# Group12_411_REV3.net
KiCad netlist of a schematic drawn in EAGLE
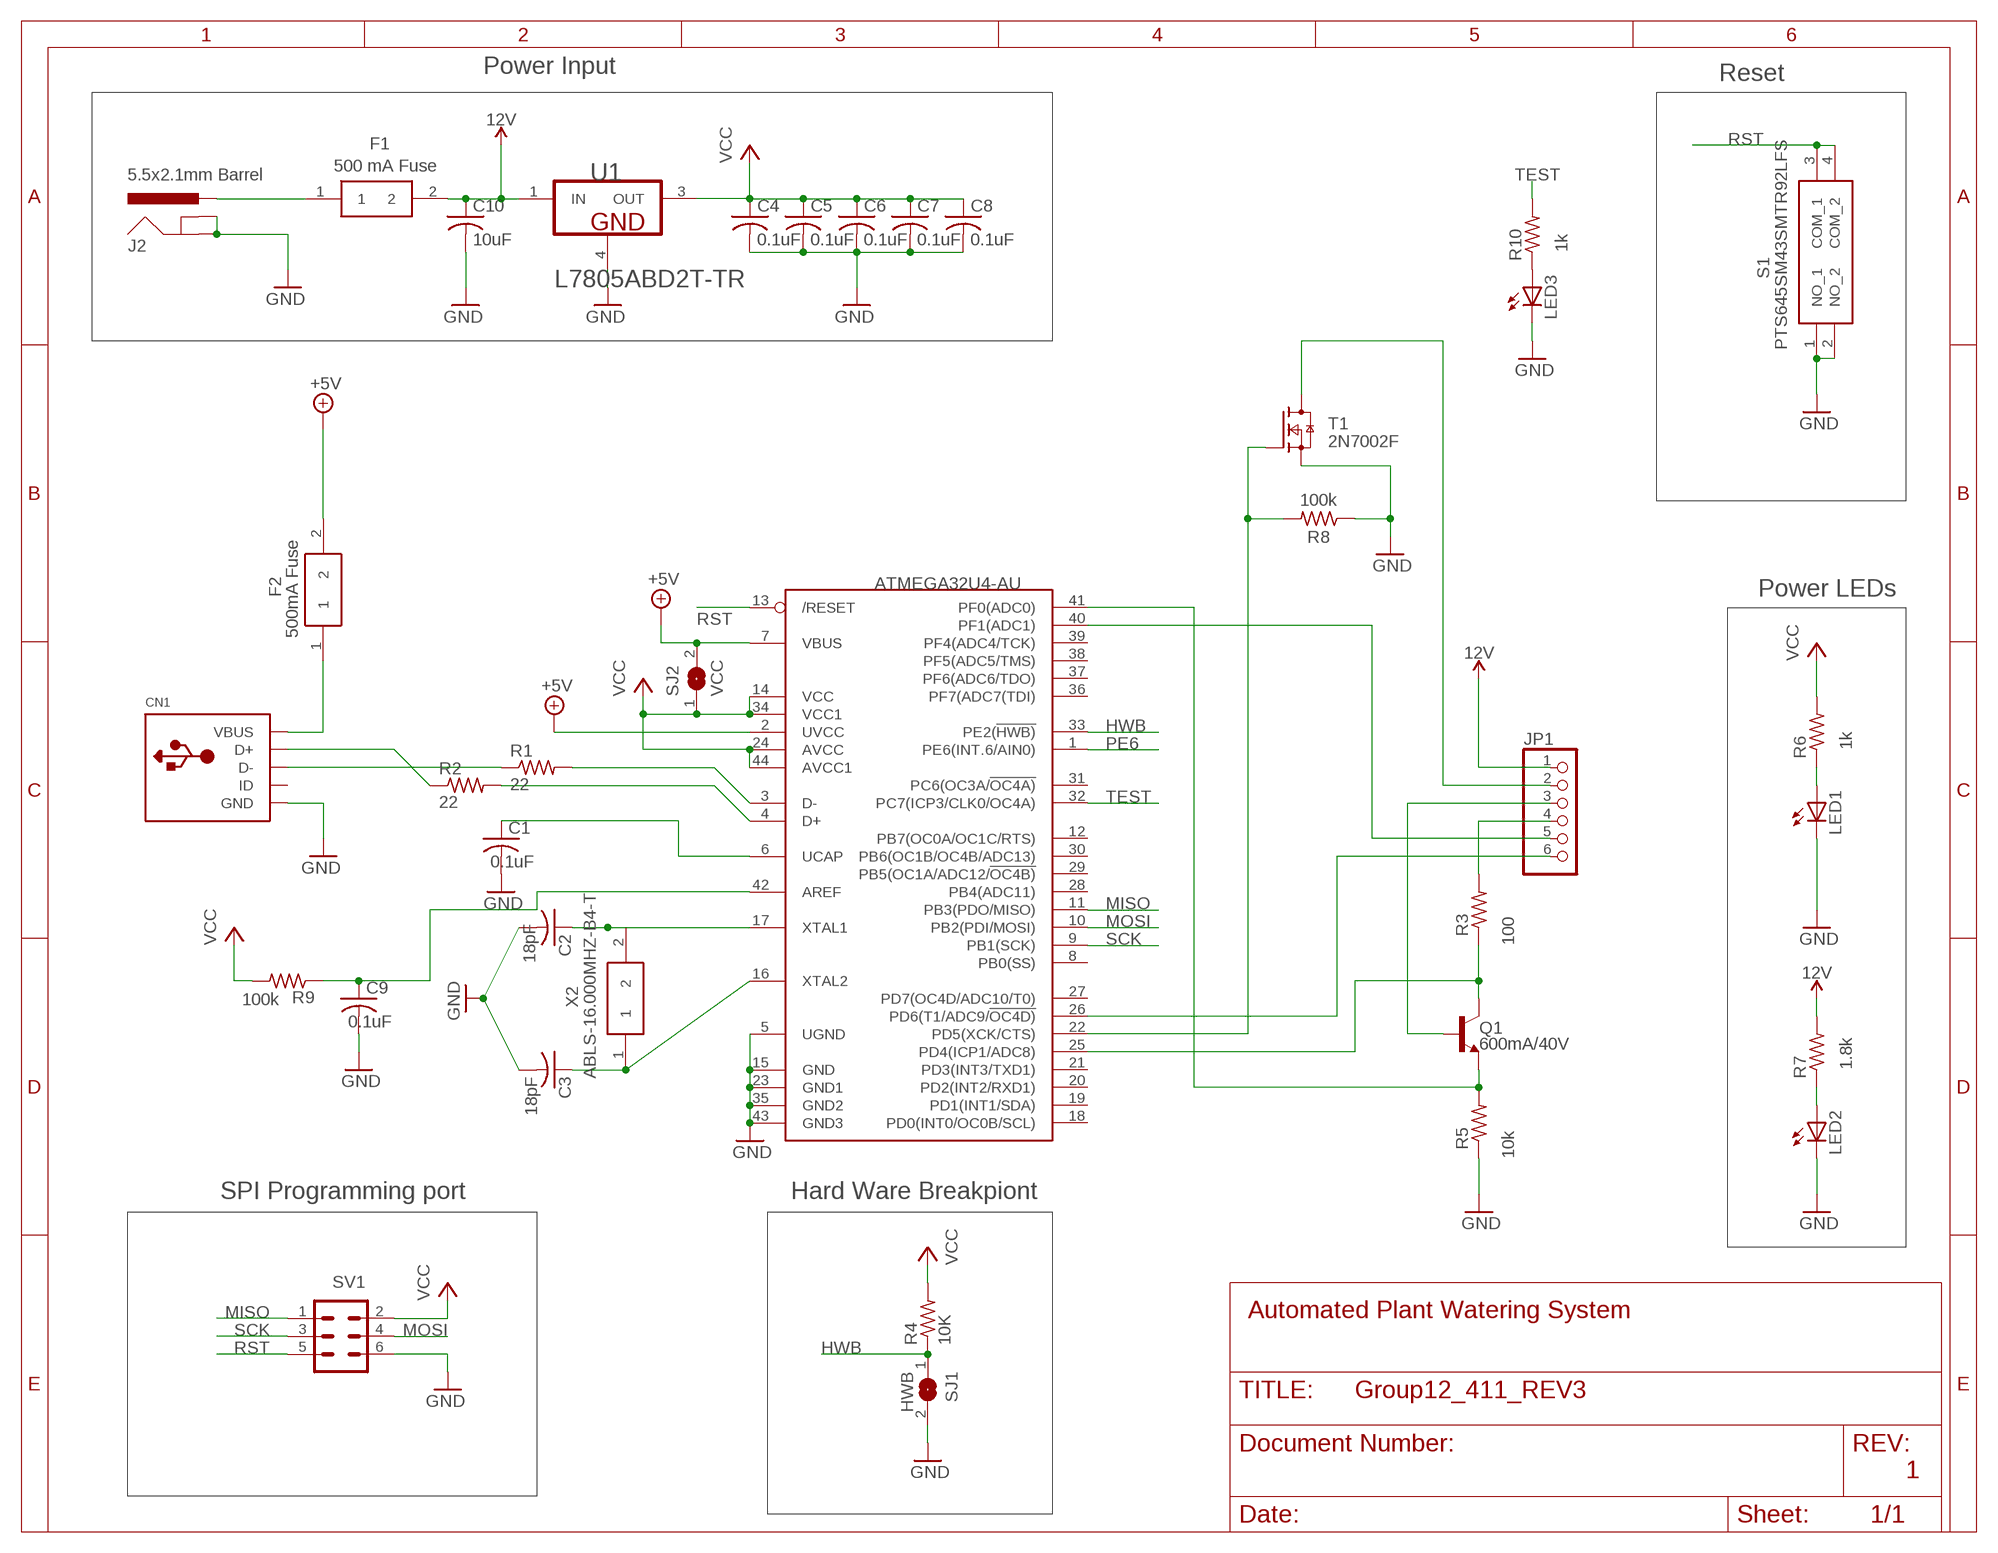
[diagram p0: schematic, sheet 1]

(export (version "E")
  (design (tool "Eeschema 10.0.6"))
  (components
    (comp (ref "C1")
      (value "0.1uF")
      (footprint "eagle-import:C0805K")
      (libsource (lib "eagle-import") (part "C-USC0805K"))
    )
    (comp (ref "C2")
      (value "18pF")
      (footprint "eagle-import:C0805K")
      (libsource (lib "eagle-import") (part "C-USC0805K"))
    )
    (comp (ref "C3")
      (value "18pF")
      (footprint "eagle-import:C0805K")
      (libsource (lib "eagle-import") (part "C-USC0805K"))
    )
    (comp (ref "C4")
      (value "0.1uF")
      (footprint "eagle-import:C0805K")
      (libsource (lib "eagle-import") (part "C-USC0805K"))
    )
    (comp (ref "C5")
      (value "0.1uF")
      (footprint "eagle-import:C0805K")
      (libsource (lib "eagle-import") (part "C-USC0805K"))
    )
    (comp (ref "C6")
      (value "0.1uF")
      (footprint "eagle-import:C0805K")
      (libsource (lib "eagle-import") (part "C-USC0805K"))
    )
    (comp (ref "C7")
      (value "0.1uF")
      (footprint "eagle-import:C0805K")
      (libsource (lib "eagle-import") (part "C-USC0805K"))
    )
    (comp (ref "C8")
      (value "0.1uF")
      (footprint "eagle-import:C0805K")
      (libsource (lib "eagle-import") (part "C-USC0805K"))
    )
    (comp (ref "C9")
      (value "0.1uF")
      (footprint "eagle-import:C0805K")
      (libsource (lib "eagle-import") (part "C-USC0805K"))
    )
    (comp (ref "C10")
      (value "10uF")
      (footprint "eagle-import:C0805K")
      (libsource (lib "eagle-import") (part "C-USC0805K"))
    )
    (comp (ref "CN1")
      (value "USBMINIB")
      (footprint "eagle-import:USB-MINIB")
      (libsource (lib "eagle-import") (part "USBMINIB"))
    )
    (comp (ref "F1")
      (value "MFU0805FF00500P100")
      (footprint "eagle-import:FUSC2012X55N")
      (fields
        (field (name "MANUFACTURER_PART_NUMBER") "MFU0805FF00500P100")
        (field (name "MOUSER_PART_NUMBER") "594-MFU0805FF00500P1")
        (field (name "MANUFACTURER_PART_NUMBER_1") "500 mA Fuse")
      )
      (libsource (lib "eagle-import") (part "MFU0805FF00500P100"))
    )
    (comp (ref "F2")
      (value "MFU0805FF00500P100")
      (footprint "eagle-import:FUSC2012X55N")
      (fields
        (field (name "MANUFACTURER_PART_NUMBER") "MFU0805FF00500P100")
        (field (name "MOUSER_PART_NUMBER") "594-MFU0805FF00500P1")
        (field (name "MANUFACTURER_PART_NUMBER_1") "500mA Fuse")
      )
      (libsource (lib "eagle-import") (part "MFU0805FF00500P100"))
    )
    (comp (ref "J2")
      (value "5.5x2.1mm Barrel")
      (footprint "eagle-import:POWER_JACK_SMD")
      (libsource (lib "eagle-import") (part "POWER_JACKSMD"))
    )
    (comp (ref "JP1")
      (value "PINHD-1X6-3.5MM")
      (footprint "eagle-import:1X06-3.5MM")
      (libsource (lib "eagle-import") (part "PINHD-1X6-3.5MM"))
    )
    (comp (ref "LED1")
      (value "LEDCHIP-LED0603")
      (footprint "eagle-import:CHIP-LED0603")
      (libsource (lib "eagle-import") (part "LEDCHIP-LED0603"))
    )
    (comp (ref "LED2")
      (value "LEDCHIP-LED0603")
      (footprint "eagle-import:CHIP-LED0603")
      (libsource (lib "eagle-import") (part "LEDCHIP-LED0603"))
    )
    (comp (ref "LED3")
      (value "LEDCHIP-LED0603")
      (footprint "eagle-import:CHIP-LED0603")
      (libsource (lib "eagle-import") (part "LEDCHIP-LED0603"))
    )
    (comp (ref "Q1")
      (value "600mA/40V")
      (footprint "eagle-import:SOT23-3")
      (libsource (lib "eagle-import") (part "TRANS_NPN-MMBT2222AL"))
    )
    (comp (ref "R1")
      (value "22")
      (footprint "eagle-import:R0805")
      (libsource (lib "eagle-import") (part "R-US_R0805"))
    )
    (comp (ref "R2")
      (value "22")
      (footprint "eagle-import:R0805")
      (libsource (lib "eagle-import") (part "R-US_R0805"))
    )
    (comp (ref "R3")
      (value "22")
      (footprint "eagle-import:R0805")
      (fields (field (name "R") "100"))
      (libsource (lib "eagle-import") (part "R-US_R0805"))
    )
    (comp (ref "R4")
      (value "10K")
      (footprint "eagle-import:R0805")
      (libsource (lib "eagle-import") (part "R-US_R0805"))
    )
    (comp (ref "R5")
      (value "22")
      (footprint "eagle-import:R0805")
      (fields (field (name "R") "10k"))
      (libsource (lib "eagle-import") (part "R-US_R0805"))
    )
    (comp (ref "R6")
      (value "10K")
      (footprint "eagle-import:R0805")
      (fields (field (name "R") "1k"))
      (libsource (lib "eagle-import") (part "R-US_R0805"))
    )
    (comp (ref "R7")
      (value "10K")
      (footprint "eagle-import:R0805")
      (fields (field (name "R") "1.8k"))
      (libsource (lib "eagle-import") (part "R-US_R0805"))
    )
    (comp (ref "R8")
      (value "10K")
      (footprint "eagle-import:R0805")
      (fields (field (name "R") "100k"))
      (libsource (lib "eagle-import") (part "R-US_R0805"))
    )
    (comp (ref "R9")
      (value "100k")
      (footprint "eagle-import:R0805")
      (libsource (lib "eagle-import") (part "R-US_R0805"))
    )
    (comp (ref "R10")
      (value "10K")
      (footprint "eagle-import:R0805")
      (fields (field (name "R") "1k"))
      (libsource (lib "eagle-import") (part "R-US_R0805"))
    )
    (comp (ref "S1")
      (value "PTS645SM43SMTR92LFS")
      (footprint "eagle-import:PTS645SMT")
      (fields (field (name "MOUSER_PART_NUMBER") "611-PTS645SM43SMTR92"))
      (libsource (lib "eagle-import") (part "PTS645SM43SMTR92LFS"))
    )
    (comp (ref "SJ1")
      (value "HWB")
      (footprint "eagle-import:SJ")
      (libsource (lib "eagle-import") (part "SJ"))
    )
    (comp (ref "SJ2")
      (value "VCC")
      (footprint "eagle-import:SJ")
      (libsource (lib "eagle-import") (part "SJ"))
    )
    (comp (ref "SV1")
      (value "MA03-2")
      (footprint "eagle-import:MA03-2")
      (libsource (lib "eagle-import") (part "MA03-2"))
    )
    (comp (ref "T1")
      (value "2N7002F")
      (footprint "eagle-import:SOT23")
      (libsource (lib "eagle-import") (part "2N7002F"))
    )
    (comp (ref "U1")
      (value "STMICROELECTRONICS_L7805ABD2T-TRSTMICROELECTRONICS_L7805ABD2T-TR_0_0")
      (footprint "eagle-import:STMICROELECTRONICS_L7805ABD2T-TR_0")
      (fields (field (name "MF") "STMicroelectronics") (field (name "MPN") "L7805ABD2T-TR"))
      (libsource (lib "eagle-import") (part "STMICROELECTRONICS_L7805ABD2T-TRSTMICROELECTRONICS_L7805ABD2T-TR_0_0"))
    )
    (comp (ref "U2")
      (value "ATMEGA32U4-AU")
      (footprint "eagle-import:TQFP44")
      (libsource (lib "eagle-import") (part "ATMEGA32U4-AU"))
    )
    (comp (ref "X2")
      (value "ABLS-16.000MHZ-B4-T")
      (footprint "eagle-import:ABLS")
      (fields (field (name "MOUSER_PART_NUMBER") "815-ABLS-16.0M-T"))
      (libsource (lib "eagle-import") (part "ABLS-16.000MHZ-B4-T"))
    )
  )
  (nets
    (net (code "1") (name "+5V") (class "Default")
      (node (ref "F2") (pin "2") (pinfunction "2_2") (pintype "bidirectional"))
      (node (ref "SJ2") (pin "2") (pinfunction "2_2") (pintype "passive"))
      (node (ref "U2") (pin "2") (pinfunction "UVCC_2") (pintype "bidirectional"))
      (node (ref "U2") (pin "7") (pinfunction "VBUS_7") (pintype "bidirectional"))
    )
    (net (code "2") (name "/HWB") (class "Default")
      (node (ref "R4") (pin "1") (pinfunction "1_1") (pintype "passive"))
      (node (ref "SJ1") (pin "1") (pinfunction "1_1") (pintype "passive"))
      (node (ref "U2") (pin "33") (pinfunction "PE2(~{HWB})_33") (pintype "bidirectional"))
    )
    (net (code "3") (name "/MISO") (class "Default")
      (node (ref "SV1") (pin "1") (pinfunction "1_1") (pintype "passive"))
      (node (ref "U2") (pin "11") (pinfunction "PB3(PDO/MISO)_11") (pintype "bidirectional"))
    )
    (net (code "4") (name "/MOSI") (class "Default")
      (node (ref "SV1") (pin "4") (pinfunction "4_4") (pintype "passive"))
      (node (ref "U2") (pin "10") (pinfunction "PB2(PDI/MOSI)_10") (pintype "bidirectional"))
    )
    (net (code "5") (name "/PE6") (class "Default")
      (node (ref "U2") (pin "1") (pinfunction "PE6(INT.6/AIN0)_1") (pintype "bidirectional"))
    )
    (net (code "6") (name "/RST") (class "Default")
      (node (ref "S1") (pin "3") (pinfunction "COM_1_3") (pintype "bidirectional"))
      (node (ref "S1") (pin "4") (pinfunction "COM_2_4") (pintype "bidirectional"))
      (node (ref "SV1") (pin "5") (pinfunction "5_5") (pintype "passive"))
      (node (ref "U2") (pin "13") (pinfunction "/RESET_13") (pintype "bidirectional"))
    )
    (net (code "7") (name "/SCK") (class "Default")
      (node (ref "SV1") (pin "3") (pinfunction "3_3") (pintype "passive"))
      (node (ref "U2") (pin "9") (pinfunction "PB1(SCK)_9") (pintype "bidirectional"))
    )
    (net (code "8") (name "/TEST") (class "Default")
      (node (ref "R10") (pin "2") (pinfunction "2_2") (pintype "passive"))
      (node (ref "U2") (pin "32") (pinfunction "PC7(ICP3/CLK0/OC4A)_32") (pintype "bidirectional"))
    )
    (net (code "9") (name "12V") (class "Default")
      (node (ref "C10") (pin "1") (pinfunction "1_1") (pintype "passive"))
      (node (ref "F1") (pin "2") (pinfunction "2_2") (pintype "bidirectional"))
      (node (ref "JP1") (pin "1") (pinfunction "1_1") (pintype "passive"))
      (node (ref "R7") (pin "2") (pinfunction "2_2") (pintype "passive"))
      (node (ref "U1") (pin "1") (pinfunction "IN_1") (pintype "power_in"))
    )
    (net (code "10") (name "GND") (class "Default")
      (node (ref "C1") (pin "2") (pinfunction "2_2") (pintype "passive"))
      (node (ref "C10") (pin "2") (pinfunction "2_2") (pintype "passive"))
      (node (ref "C2") (pin "2") (pinfunction "2_2") (pintype "passive"))
      (node (ref "C3") (pin "2") (pinfunction "2_2") (pintype "passive"))
      (node (ref "C4") (pin "2") (pinfunction "2_2") (pintype "passive"))
      (node (ref "C5") (pin "2") (pinfunction "2_2") (pintype "passive"))
      (node (ref "C6") (pin "2") (pinfunction "2_2") (pintype "passive"))
      (node (ref "C7") (pin "2") (pinfunction "2_2") (pintype "passive"))
      (node (ref "C8") (pin "2") (pinfunction "2_2") (pintype "passive"))
      (node (ref "C9") (pin "2") (pinfunction "2_2") (pintype "passive"))
      (node (ref "CN1") (pin "GND") (pinfunction "GND_GND") (pintype "power_in"))
      (node (ref "J2") (pin "GND") (pinfunction "GNDBREAK_GND") (pintype "bidirectional"))
      (node (ref "J2") (pin "P$4") (pinfunction "GND_P$4") (pintype "bidirectional"))
      (node (ref "LED1") (pin "C") (pinfunction "C_C") (pintype "passive"))
      (node (ref "LED2") (pin "C") (pinfunction "C_C") (pintype "passive"))
      (node (ref "LED3") (pin "C") (pinfunction "C_C") (pintype "passive"))
      (node (ref "R5") (pin "1") (pinfunction "1_1") (pintype "passive"))
      (node (ref "R8") (pin "1") (pinfunction "1_1") (pintype "passive"))
      (node (ref "S1") (pin "1") (pinfunction "NO_1_1") (pintype "bidirectional"))
      (node (ref "S1") (pin "2") (pinfunction "NO_2_2") (pintype "bidirectional"))
      (node (ref "SJ1") (pin "2") (pinfunction "2_2") (pintype "passive"))
      (node (ref "SV1") (pin "6") (pinfunction "6_6") (pintype "passive"))
      (node (ref "T1") (pin "2") (pinfunction "S_2") (pintype "passive"))
      (node (ref "U1") (pin "4") (pinfunction "GND_4") (pintype "power_in"))
      (node (ref "U2") (pin "15") (pinfunction "GND_15") (pintype "bidirectional"))
      (node (ref "U2") (pin "23") (pinfunction "GND1_23") (pintype "bidirectional"))
      (node (ref "U2") (pin "35") (pinfunction "GND2_35") (pintype "bidirectional"))
      (node (ref "U2") (pin "43") (pinfunction "GND3_43") (pintype "bidirectional"))
      (node (ref "U2") (pin "5") (pinfunction "UGND_5") (pintype "bidirectional"))
    )
    (net (code "11") (name "Net-(CN1-PadD+)") (class "Default")
      (node (ref "CN1") (pin "D+") (pinfunction "D+_D+") (pintype "bidirectional"))
      (node (ref "R2") (pin "1") (pinfunction "1_1") (pintype "passive"))
    )
    (net (code "12") (name "Net-(CN1-PadD-)") (class "Default")
      (node (ref "CN1") (pin "D-") (pinfunction "D-_D-") (pintype "bidirectional"))
      (node (ref "R1") (pin "1") (pinfunction "1_1") (pintype "passive"))
    )
    (net (code "13") (name "Net-(CN1-PadVBUS)") (class "Default")
      (node (ref "CN1") (pin "VBUS") (pinfunction "VBUS_VBUS") (pintype "power_in"))
      (node (ref "F2") (pin "1") (pinfunction "1_1") (pintype "bidirectional"))
    )
    (net (code "14") (name "Net-(J2-PWR)") (class "Default")
      (node (ref "F1") (pin "1") (pinfunction "1_1") (pintype "bidirectional"))
      (node (ref "J2") (pin "VIN0") (pinfunction "PWR_VIN0") (pintype "bidirectional"))
    )
    (net (code "15") (name "Net-(JP1-Pad4)") (class "Default")
      (node (ref "JP1") (pin "4") (pinfunction "4_4") (pintype "passive"))
      (node (ref "R3") (pin "2") (pinfunction "2_2") (pintype "passive"))
    )
    (net (code "16") (name "Net-(LED1-PadA)") (class "Default")
      (node (ref "LED1") (pin "A") (pinfunction "A_A") (pintype "passive"))
      (node (ref "R6") (pin "1") (pinfunction "1_1") (pintype "passive"))
    )
    (net (code "17") (name "Net-(LED2-PadA)") (class "Default")
      (node (ref "LED2") (pin "A") (pinfunction "A_A") (pintype "passive"))
      (node (ref "R7") (pin "1") (pinfunction "1_1") (pintype "passive"))
    )
    (net (code "18") (name "Net-(LED3-PadA)") (class "Default")
      (node (ref "LED3") (pin "A") (pinfunction "A_A") (pintype "passive"))
      (node (ref "R10") (pin "1") (pinfunction "1_1") (pintype "passive"))
    )
    (net (code "19") (name "Net-(Q1-B)") (class "Default")
      (node (ref "JP1") (pin "3") (pinfunction "3_3") (pintype "passive"))
      (node (ref "Q1") (pin "1") (pinfunction "B_1") (pintype "passive"))
    )
    (net (code "20") (name "Net-(Q1-C)") (class "Default")
      (node (ref "Q1") (pin "3") (pinfunction "C_3") (pintype "passive"))
      (node (ref "R3") (pin "1") (pinfunction "1_1") (pintype "passive"))
      (node (ref "U2") (pin "25") (pinfunction "PD4(ICP1/ADC8)_25") (pintype "bidirectional"))
    )
    (net (code "21") (name "Net-(Q1-E)") (class "Default")
      (node (ref "Q1") (pin "2") (pinfunction "E_2") (pintype "passive"))
      (node (ref "R5") (pin "2") (pinfunction "2_2") (pintype "passive"))
      (node (ref "U2") (pin "41") (pinfunction "PF0(ADC0)_41") (pintype "bidirectional"))
    )
    (net (code "22") (name "Net-(T1-D)") (class "Default")
      (node (ref "JP1") (pin "2") (pinfunction "2_2") (pintype "passive"))
      (node (ref "T1") (pin "3") (pinfunction "D_3") (pintype "passive"))
    )
    (net (code "23") (name "Net-(T1-G)") (class "Default")
      (node (ref "R8") (pin "2") (pinfunction "2_2") (pintype "passive"))
      (node (ref "T1") (pin "1") (pinfunction "G_1") (pintype "passive"))
      (node (ref "U2") (pin "22") (pinfunction "PD5(XCK/CTS)_22") (pintype "bidirectional"))
    )
    (net (code "24") (name "Net-(U2-AREF)") (class "Default")
      (node (ref "C9") (pin "1") (pinfunction "1_1") (pintype "passive"))
      (node (ref "R9") (pin "1") (pinfunction "1_1") (pintype "passive"))
      (node (ref "U2") (pin "42") (pinfunction "AREF_42") (pintype "bidirectional"))
    )
    (net (code "25") (name "Net-(U2-D+)") (class "Default")
      (node (ref "R2") (pin "2") (pinfunction "2_2") (pintype "passive"))
      (node (ref "U2") (pin "4") (pinfunction "D+_4") (pintype "bidirectional"))
    )
    (net (code "26") (name "Net-(U2-D-)") (class "Default")
      (node (ref "R1") (pin "2") (pinfunction "2_2") (pintype "passive"))
      (node (ref "U2") (pin "3") (pinfunction "D-_3") (pintype "bidirectional"))
    )
    (net (code "27") (name "Net-(U2-PD6(T1{slash}ADC9{slash}~{OC4D}))") (class "Default")
      (node (ref "JP1") (pin "6") (pinfunction "6_6") (pintype "passive"))
      (node (ref "U2") (pin "26") (pinfunction "PD6(T1/ADC9/~{OC4D})_26") (pintype "bidirectional"))
    )
    (net (code "28") (name "Net-(U2-PF1(ADC1))") (class "Default")
      (node (ref "JP1") (pin "5") (pinfunction "5_5") (pintype "passive"))
      (node (ref "U2") (pin "40") (pinfunction "PF1(ADC1)_40") (pintype "bidirectional"))
    )
    (net (code "29") (name "Net-(U2-UCAP)") (class "Default")
      (node (ref "C1") (pin "1") (pinfunction "1_1") (pintype "passive"))
      (node (ref "U2") (pin "6") (pinfunction "UCAP_6") (pintype "bidirectional"))
    )
    (net (code "30") (name "Net-(U2-XTAL1)") (class "Default")
      (node (ref "C2") (pin "1") (pinfunction "1_1") (pintype "passive"))
      (node (ref "U2") (pin "17") (pinfunction "XTAL1_17") (pintype "bidirectional"))
      (node (ref "X2") (pin "2") (pinfunction "2_2") (pintype "bidirectional"))
    )
    (net (code "31") (name "Net-(U2-XTAL2)") (class "Default")
      (node (ref "C3") (pin "1") (pinfunction "1_1") (pintype "passive"))
      (node (ref "U2") (pin "16") (pinfunction "XTAL2_16") (pintype "bidirectional"))
      (node (ref "X2") (pin "1") (pinfunction "1_1") (pintype "bidirectional"))
    )
    (net (code "32") (name "VCC") (class "Default")
      (node (ref "C4") (pin "1") (pinfunction "1_1") (pintype "passive"))
      (node (ref "C5") (pin "1") (pinfunction "1_1") (pintype "passive"))
      (node (ref "C6") (pin "1") (pinfunction "1_1") (pintype "passive"))
      (node (ref "C7") (pin "1") (pinfunction "1_1") (pintype "passive"))
      (node (ref "C8") (pin "1") (pinfunction "1_1") (pintype "passive"))
      (node (ref "R4") (pin "2") (pinfunction "2_2") (pintype "passive"))
      (node (ref "R6") (pin "2") (pinfunction "2_2") (pintype "passive"))
      (node (ref "R9") (pin "2") (pinfunction "2_2") (pintype "passive"))
      (node (ref "SJ2") (pin "1") (pinfunction "1_1") (pintype "passive"))
      (node (ref "SV1") (pin "2") (pinfunction "2_2") (pintype "passive"))
      (node (ref "U1") (pin "3") (pinfunction "OUT_3") (pintype "power_in"))
      (node (ref "U2") (pin "14") (pinfunction "VCC_14") (pintype "bidirectional"))
      (node (ref "U2") (pin "24") (pinfunction "AVCC_24") (pintype "bidirectional"))
      (node (ref "U2") (pin "34") (pinfunction "VCC1_34") (pintype "bidirectional"))
      (node (ref "U2") (pin "44") (pinfunction "AVCC1_44") (pintype "bidirectional"))
    )
    (net (code "33") (name "unconnected-(CN1-PadID)") (class "Default")
      (node (ref "CN1") (pin "ID") (pinfunction "ID_ID") (pintype "bidirectional"))
    )
    (net (code "34") (name "unconnected-(U2-PB0(SS)-Pad8)") (class "Default")
      (node (ref "U2") (pin "8") (pinfunction "PB0(SS)_8") (pintype "bidirectional"))
    )
    (net (code "35") (name "unconnected-(U2-PB4(ADC11)-Pad28)") (class "Default")
      (node (ref "U2") (pin "28") (pinfunction "PB4(ADC11)_28") (pintype "bidirectional"))
    )
    (net (code "36") (name "unconnected-(U2-PB5(OC1A{slash}ADC12{slash}~{OC4B})-Pad29)") (class "Default")
      (node (ref "U2") (pin "29") (pinfunction "PB5(OC1A/ADC12/~{OC4B})_29") (pintype "bidirectional"))
    )
    (net (code "37") (name "unconnected-(U2-PB6(OC1B{slash}OC4B{slash}ADC13)-Pad30)") (class "Default")
      (node (ref "U2") (pin "30") (pinfunction "PB6(OC1B/OC4B/ADC13)_30") (pintype "bidirectional"))
    )
    (net (code "38") (name "unconnected-(U2-PB7(OC0A{slash}OC1C{slash}RTS)-Pad12)") (class "Default")
      (node (ref "U2") (pin "12") (pinfunction "PB7(OC0A/OC1C/RTS)_12") (pintype "bidirectional"))
    )
    (net (code "39") (name "unconnected-(U2-PC6(OC3A{slash}~{OC4A})-Pad31)") (class "Default")
      (node (ref "U2") (pin "31") (pinfunction "PC6(OC3A/~{OC4A})_31") (pintype "bidirectional"))
    )
    (net (code "40") (name "unconnected-(U2-PD0(INT0{slash}OC0B{slash}SCL)-Pad18)") (class "Default")
      (node (ref "U2") (pin "18") (pinfunction "PD0(INT0/OC0B/SCL)_18") (pintype "bidirectional"))
    )
    (net (code "41") (name "unconnected-(U2-PD1(INT1{slash}SDA)-Pad19)") (class "Default")
      (node (ref "U2") (pin "19") (pinfunction "PD1(INT1/SDA)_19") (pintype "bidirectional"))
    )
    (net (code "42") (name "unconnected-(U2-PD2(INT2{slash}RXD1)-Pad20)") (class "Default")
      (node (ref "U2") (pin "20") (pinfunction "PD2(INT2/RXD1)_20") (pintype "bidirectional"))
    )
    (net (code "43") (name "unconnected-(U2-PD3(INT3{slash}TXD1)-Pad21)") (class "Default")
      (node (ref "U2") (pin "21") (pinfunction "PD3(INT3/TXD1)_21") (pintype "bidirectional"))
    )
    (net (code "44") (name "unconnected-(U2-PD7(OC4D{slash}ADC10{slash}T0)-Pad27)") (class "Default")
      (node (ref "U2") (pin "27") (pinfunction "PD7(OC4D/ADC10/T0)_27") (pintype "bidirectional"))
    )
    (net (code "45") (name "unconnected-(U2-PF4(ADC4{slash}TCK)-Pad39)") (class "Default")
      (node (ref "U2") (pin "39") (pinfunction "PF4(ADC4/TCK)_39") (pintype "bidirectional"))
    )
    (net (code "46") (name "unconnected-(U2-PF5(ADC5{slash}TMS)-Pad38)") (class "Default")
      (node (ref "U2") (pin "38") (pinfunction "PF5(ADC5/TMS)_38") (pintype "bidirectional"))
    )
    (net (code "47") (name "unconnected-(U2-PF6(ADC6{slash}TDO)-Pad37)") (class "Default")
      (node (ref "U2") (pin "37") (pinfunction "PF6(ADC6/TDO)_37") (pintype "bidirectional"))
    )
    (net (code "48") (name "unconnected-(U2-PF7(ADC7(TDI)-Pad36)") (class "Default")
      (node (ref "U2") (pin "36") (pinfunction "PF7(ADC7(TDI)_36") (pintype "bidirectional"))
    )
  )
)
